# NCS_Wireless_Control_Card_MCU.net
KiCad netlist of a schematic drawn in Altium Designer
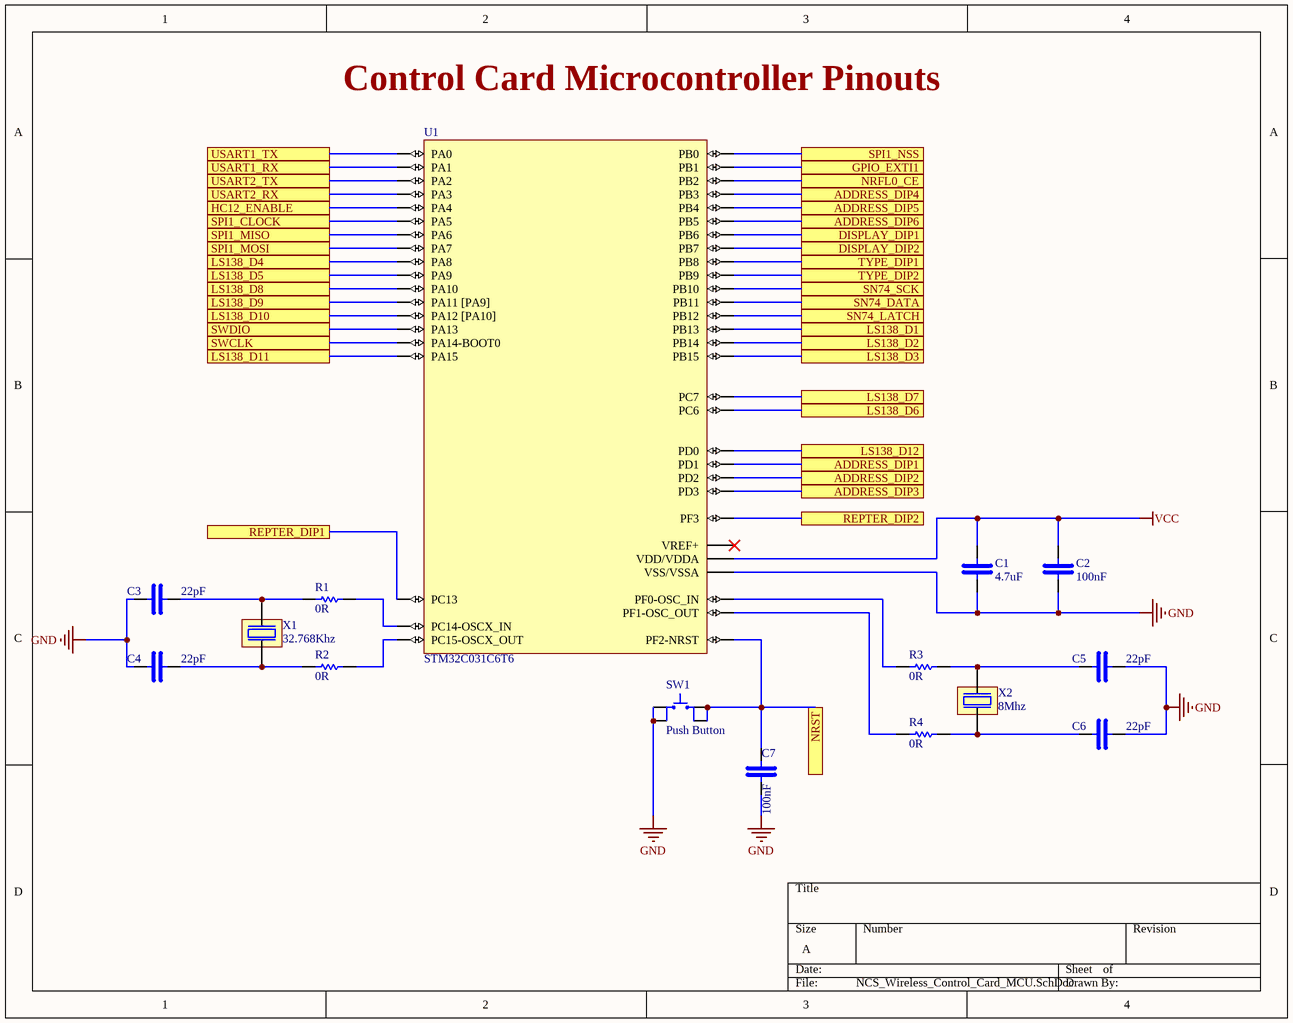
[diagram p0: NCS_Wireless_Control_Card_MCU.SchDoc]

(export (version "E")
  (design (tool "Eeschema 10.0.6"))
  (components
    (comp (ref "C1")
      (value "4.7uF")
      (footprint "C0805C209D3HACTU_2pF")
      (description "Multilayer Ceramic Capacitor, 4.7 uF, 25 V, ï¿½ 10%, X5R, 0805 [2012 Metric]")
      (fields
        (field (name "MANUFACTURER") "KEMET")
        (field (name "MANUFACTURER PART NUMBER") "C0805C475K3PACTU")
      )
      (libsource (lib "schlib") (part "C0805C475K3PACTU"))
    )
    (comp (ref "C2")
      (value "100nF")
      (footprint "C0805C104K3RACTU_100nF")
      (description "Multilayer Ceramic Capacitor, 0.1 uF, 25 V, ï¿½ 10%, X7R, 0805 [2012 Metric]")
      (fields
        (field (name "MANUFACTURER") "KEMET")
        (field (name "MANUFACTURER PART NUMBER") "C0805C104K3RACTU")
      )
      (libsource (lib "schlib") (part "C0805C104K3RACTU"))
    )
    (comp (ref "C3")
      (value "22pF")
      (footprint "C0805C209D3HACTU_2pF")
      (description "C0805C209D3HACTU_2pF")
      (fields
        (field (name "MANUFACTURER") "KEMET")
        (field (name "MANUFACTURER PART NUMBER") "C0805C209D3HACTU")
      )
      (libsource (lib "schlib") (part "C0805C209D3HACTU"))
    )
    (comp (ref "C4")
      (value "22pF")
      (footprint "C0805C209D3HACTU_2pF")
      (description "C0805C209D3HACTU_2pF")
      (fields
        (field (name "MANUFACTURER") "KEMET")
        (field (name "MANUFACTURER PART NUMBER") "C0805C209D3HACTU")
      )
      (libsource (lib "schlib") (part "C0805C209D3HACTU"))
    )
    (comp (ref "C5")
      (value "22pF")
      (footprint "C0805C209D3HACTU_2pF")
      (description "C0805C209D3HACTU_2pF")
      (fields
        (field (name "MANUFACTURER") "KEMET")
        (field (name "MANUFACTURER PART NUMBER") "C0805C209D3HACTU")
      )
      (libsource (lib "schlib") (part "C0805C209D3HACTU"))
    )
    (comp (ref "C6")
      (value "22pF")
      (footprint "C0805C209D3HACTU_2pF")
      (description "C0805C209D3HACTU_2pF")
      (fields
        (field (name "MANUFACTURER") "KEMET")
        (field (name "MANUFACTURER PART NUMBER") "C0805C209D3HACTU")
      )
      (libsource (lib "schlib") (part "C0805C209D3HACTU"))
    )
    (comp (ref "C7")
      (value "100nF")
      (footprint "C0805C104K3RACTU_100nF")
      (description "Multilayer Ceramic Capacitor, 0.1 uF, 25 V, ï¿½ 10%, X7R, 0805 [2012 Metric]")
      (fields
        (field (name "MANUFACTURER") "KEMET")
        (field (name "MANUFACTURER PART NUMBER") "C0805C104K3RACTU")
      )
      (libsource (lib "schlib") (part "C0805C104K3RACTU"))
    )
    (comp (ref "R1")
      (value "0R")
      (footprint "RC0805FR-7W330RL")
      (description "Res Thick Film 0805 330 Ohm 1% 0.25W(1/4W) ±200ppm/C Pad SMD T/R")
      (fields
        (field (name "MANUFACTURER") "Yageo")
        (field (name "MANUFACTURER PART NUMBER") "RC0805FR-7W330RL")
      )
      (libsource (lib "schlib") (part "RC0805FR-7W330RL"))
    )
    (comp (ref "R2")
      (value "0R")
      (footprint "RC0805FR-7W330RL")
      (description "Res Thick Film 0805 330 Ohm 1% 0.25W(1/4W) ±200ppm/C Pad SMD T/R")
      (fields
        (field (name "MANUFACTURER") "Yageo")
        (field (name "MANUFACTURER PART NUMBER") "RC0805FR-7W330RL")
      )
      (libsource (lib "schlib") (part "RC0805FR-7W330RL"))
    )
    (comp (ref "R3")
      (value "0R")
      (footprint "RC0805FR-7W330RL")
      (description "Res Thick Film 0805 330 Ohm 1% 0.25W(1/4W) ±200ppm/C Pad SMD T/R")
      (fields
        (field (name "MANUFACTURER") "Yageo")
        (field (name "MANUFACTURER PART NUMBER") "RC0805FR-7W330RL")
      )
      (libsource (lib "schlib") (part "RC0805FR-7W330RL"))
    )
    (comp (ref "R4")
      (value "0R")
      (footprint "RC0805FR-7W330RL")
      (description "Res Thick Film 0805 330 Ohm 1% 0.25W(1/4W) ±200ppm/C Pad SMD T/R")
      (fields
        (field (name "MANUFACTURER") "Yageo")
        (field (name "MANUFACTURER PART NUMBER") "RC0805FR-7W330RL")
      )
      (libsource (lib "schlib") (part "RC0805FR-7W330RL"))
    )
    (comp (ref "SW1")
      (value "Push Button")
      (footprint "PUSH BUTTON SMD")
      (libsource (lib "NCS_Wireless_Bed_Unit") (part "Tactile Switch SMD 4P 5.2x5.2x1.5mm - EVELTA"))
    )
    (comp (ref "U1")
      (value "STM32C031C6T6")
      (footprint "STM32C031C6T6-48N")
      (description "RISC Microcontroller, 32-Bit, FLASH, CORTEX-M4F CPU, 180MHz, CMOS, PBGA216")
      (fields (field (name "MANUFACTURER") "STMicroelectronics"))
      (libsource (lib "NCS_Wireless_Bed_Unit") (part "STM32C031C6T6"))
    )
    (comp (ref "X1")
      (value "32.768Khz")
      (footprint "32.768KHz")
      (libsource (lib "NCS_Wireless_Bed_Unit") (part "32.768 Khz RTC Crystal T38-SUNROM"))
    )
    (comp (ref "X2")
      (value "8Mhz")
      (footprint "8Mhz Crystal")
      (libsource (lib "NCS_Wireless_Bed_Unit") (part "8 Mhz Crystal HC-49US-SUNROM"))
    )
  )
  (nets
    (net (code "1") (name "/ADDRESS_DIP1") (class "Default")
      (node (ref "U1") (pin "39") (pinfunction "PD1_39") (pintype "bidirectional"))
    )
    (net (code "2") (name "/ADDRESS_DIP2") (class "Default")
      (node (ref "U1") (pin "40") (pinfunction "PD2_40") (pintype "bidirectional"))
    )
    (net (code "3") (name "/ADDRESS_DIP3") (class "Default")
      (node (ref "U1") (pin "41") (pinfunction "PD3_41") (pintype "bidirectional"))
    )
    (net (code "4") (name "/ADDRESS_DIP4") (class "Default")
      (node (ref "U1") (pin "42") (pinfunction "PB3_42") (pintype "bidirectional"))
    )
    (net (code "5") (name "/ADDRESS_DIP5") (class "Default")
      (node (ref "U1") (pin "43") (pinfunction "PB4_43") (pintype "bidirectional"))
    )
    (net (code "6") (name "/ADDRESS_DIP6") (class "Default")
      (node (ref "U1") (pin "44") (pinfunction "PB5_44") (pintype "bidirectional"))
    )
    (net (code "7") (name "/DISPLAY_DIP1") (class "Default")
      (node (ref "U1") (pin "45") (pinfunction "PB6_45") (pintype "bidirectional"))
    )
    (net (code "8") (name "/DISPLAY_DIP2") (class "Default")
      (node (ref "U1") (pin "46") (pinfunction "PB7_46") (pintype "bidirectional"))
    )
    (net (code "9") (name "/GPIO_EXTI1") (class "Default")
      (node (ref "U1") (pin "20") (pinfunction "PB1_20") (pintype "bidirectional"))
    )
    (net (code "10") (name "/HC12_ENABLE") (class "Default")
      (node (ref "U1") (pin "15") (pinfunction "PA4_15") (pintype "bidirectional"))
    )
    (net (code "11") (name "/LS138_D1") (class "Default")
      (node (ref "U1") (pin "25") (pinfunction "PB13_25") (pintype "bidirectional"))
    )
    (net (code "12") (name "/LS138_D2") (class "Default")
      (node (ref "U1") (pin "26") (pinfunction "PB14_26") (pintype "bidirectional"))
    )
    (net (code "13") (name "/LS138_D3") (class "Default")
      (node (ref "U1") (pin "27") (pinfunction "PB15_27") (pintype "bidirectional"))
    )
    (net (code "14") (name "/LS138_D4") (class "Default")
      (node (ref "U1") (pin "28") (pinfunction "PA8_28") (pintype "bidirectional"))
    )
    (net (code "15") (name "/LS138_D5") (class "Default")
      (node (ref "U1") (pin "29") (pinfunction "PA9_29") (pintype "bidirectional"))
    )
    (net (code "16") (name "/LS138_D6") (class "Default")
      (node (ref "U1") (pin "30") (pinfunction "PC6_30") (pintype "bidirectional"))
    )
    (net (code "17") (name "/LS138_D7") (class "Default")
      (node (ref "U1") (pin "31") (pinfunction "PC7_31") (pintype "bidirectional"))
    )
    (net (code "18") (name "/LS138_D8") (class "Default")
      (node (ref "U1") (pin "32") (pinfunction "PA10_32") (pintype "bidirectional"))
    )
    (net (code "19") (name "/LS138_D9") (class "Default")
      (node (ref "U1") (pin "33") (pinfunction "PA11_[PA9]_33") (pintype "bidirectional"))
    )
    (net (code "20") (name "/LS138_D10") (class "Default")
      (node (ref "U1") (pin "34") (pinfunction "PA12_[PA10]_34") (pintype "bidirectional"))
    )
    (net (code "21") (name "/LS138_D11") (class "Default")
      (node (ref "U1") (pin "37") (pinfunction "PA15_37") (pintype "bidirectional"))
    )
    (net (code "22") (name "/LS138_D12") (class "Default")
      (node (ref "U1") (pin "38") (pinfunction "PD0_38") (pintype "bidirectional"))
    )
    (net (code "23") (name "/NRFL0_CE") (class "Default")
      (node (ref "U1") (pin "21") (pinfunction "PB2_21") (pintype "bidirectional"))
    )
    (net (code "24") (name "/NRST") (class "Default")
      (node (ref "C7") (pin "2") (pinfunction "2_2") (pintype "passive"))
      (node (ref "SW1") (pin "3") (pinfunction "3_3") (pintype "passive"))
      (node (ref "SW1") (pin "4") (pinfunction "4_4") (pintype "passive"))
      (node (ref "U1") (pin "10") (pinfunction "PF2-NRST_10") (pintype "bidirectional"))
    )
    (net (code "25") (name "/REPTER_DIP1") (class "Default")
      (node (ref "U1") (pin "1") (pinfunction "PC13_1") (pintype "bidirectional"))
    )
    (net (code "26") (name "/REPTER_DIP2") (class "Default")
      (node (ref "U1") (pin "4") (pinfunction "PF3_4") (pintype "bidirectional"))
    )
    (net (code "27") (name "/SN74_DATA") (class "Default")
      (node (ref "U1") (pin "23") (pinfunction "PB11_23") (pintype "bidirectional"))
    )
    (net (code "28") (name "/SN74_LATCH") (class "Default")
      (node (ref "U1") (pin "24") (pinfunction "PB12_24") (pintype "bidirectional"))
    )
    (net (code "29") (name "/SN74_SCK") (class "Default")
      (node (ref "U1") (pin "22") (pinfunction "PB10_22") (pintype "bidirectional"))
    )
    (net (code "30") (name "/SPI1_CLOCK") (class "Default")
      (node (ref "U1") (pin "16") (pinfunction "PA5_16") (pintype "bidirectional"))
    )
    (net (code "31") (name "/SPI1_MISO") (class "Default")
      (node (ref "U1") (pin "17") (pinfunction "PA6_17") (pintype "bidirectional"))
    )
    (net (code "32") (name "/SPI1_MOSI") (class "Default")
      (node (ref "U1") (pin "18") (pinfunction "PA7_18") (pintype "bidirectional"))
    )
    (net (code "33") (name "/SPI1_NSS") (class "Default")
      (node (ref "U1") (pin "19") (pinfunction "PB0_19") (pintype "bidirectional"))
    )
    (net (code "34") (name "/SWCLK") (class "Default")
      (node (ref "U1") (pin "36") (pinfunction "PA14-BOOT0_36") (pintype "bidirectional"))
    )
    (net (code "35") (name "/SWDIO") (class "Default")
      (node (ref "U1") (pin "35") (pinfunction "PA13_35") (pintype "bidirectional"))
    )
    (net (code "36") (name "/TYPE_DIP1") (class "Default")
      (node (ref "U1") (pin "47") (pinfunction "PB8_47") (pintype "bidirectional"))
    )
    (net (code "37") (name "/TYPE_DIP2") (class "Default")
      (node (ref "U1") (pin "48") (pinfunction "PB9_48") (pintype "bidirectional"))
    )
    (net (code "38") (name "/USART1_RX") (class "Default")
      (node (ref "U1") (pin "12") (pinfunction "PA1_12") (pintype "bidirectional"))
    )
    (net (code "39") (name "/USART1_TX") (class "Default")
      (node (ref "U1") (pin "11") (pinfunction "PA0_11") (pintype "bidirectional"))
    )
    (net (code "40") (name "/USART2_RX") (class "Default")
      (node (ref "U1") (pin "14") (pinfunction "PA3_14") (pintype "bidirectional"))
    )
    (net (code "41") (name "/USART2_TX") (class "Default")
      (node (ref "U1") (pin "13") (pinfunction "PA2_13") (pintype "bidirectional"))
    )
    (net (code "42") (name "GND") (class "Default")
      (node (ref "C1") (pin "1") (pinfunction "1_1") (pintype "passive"))
      (node (ref "C2") (pin "1") (pinfunction "1_1") (pintype "passive"))
      (node (ref "C3") (pin "2") (pinfunction "2_2") (pintype "passive"))
      (node (ref "C4") (pin "2") (pinfunction "2_2") (pintype "passive"))
      (node (ref "C5") (pin "1") (pinfunction "1_1") (pintype "passive"))
      (node (ref "C6") (pin "1") (pinfunction "1_1") (pintype "passive"))
      (node (ref "C7") (pin "1") (pinfunction "1_1") (pintype "passive"))
      (node (ref "SW1") (pin "1") (pinfunction "1_1") (pintype "passive"))
      (node (ref "SW1") (pin "2") (pinfunction "2_2") (pintype "passive"))
      (node (ref "U1") (pin "7") (pinfunction "VSS/VSSA_7") (pintype "power_in"))
    )
    (net (code "43") (name "Net-(C3-Pad1)") (class "Default")
      (node (ref "C3") (pin "1") (pinfunction "1_1") (pintype "passive"))
      (node (ref "R1") (pin "1") (pinfunction "1_1") (pintype "passive"))
      (node (ref "X1") (pin "2") (pinfunction "2_2") (pintype "passive"))
    )
    (net (code "44") (name "Net-(C4-Pad1)") (class "Default")
      (node (ref "C4") (pin "1") (pinfunction "1_1") (pintype "passive"))
      (node (ref "R2") (pin "1") (pinfunction "1_1") (pintype "passive"))
      (node (ref "X1") (pin "1") (pinfunction "1_1") (pintype "passive"))
    )
    (net (code "45") (name "Net-(C5-Pad2)") (class "Default")
      (node (ref "C5") (pin "2") (pinfunction "2_2") (pintype "passive"))
      (node (ref "R3") (pin "2") (pinfunction "2_2") (pintype "passive"))
      (node (ref "X2") (pin "2") (pinfunction "2_2") (pintype "passive"))
    )
    (net (code "46") (name "Net-(C6-Pad2)") (class "Default")
      (node (ref "C6") (pin "2") (pinfunction "2_2") (pintype "passive"))
      (node (ref "R4") (pin "2") (pinfunction "2_2") (pintype "passive"))
      (node (ref "X2") (pin "1") (pinfunction "1_1") (pintype "passive"))
    )
    (net (code "47") (name "Net-(U1-PC14-OSCX_IN)") (class "Default")
      (node (ref "R1") (pin "2") (pinfunction "2_2") (pintype "passive"))
      (node (ref "U1") (pin "2") (pinfunction "PC14-OSCX_IN_2") (pintype "bidirectional"))
    )
    (net (code "48") (name "Net-(U1-PC15-OSCX_OUT)") (class "Default")
      (node (ref "R2") (pin "2") (pinfunction "2_2") (pintype "passive"))
      (node (ref "U1") (pin "3") (pinfunction "PC15-OSCX_OUT_3") (pintype "bidirectional"))
    )
    (net (code "49") (name "Net-(U1-PF0-OSC_IN)") (class "Default")
      (node (ref "R3") (pin "1") (pinfunction "1_1") (pintype "passive"))
      (node (ref "U1") (pin "8") (pinfunction "PF0-OSC_IN_8") (pintype "bidirectional"))
    )
    (net (code "50") (name "Net-(U1-PF1-OSC_OUT)") (class "Default")
      (node (ref "R4") (pin "1") (pinfunction "1_1") (pintype "passive"))
      (node (ref "U1") (pin "9") (pinfunction "PF1-OSC_OUT_9") (pintype "bidirectional"))
    )
    (net (code "51") (name "VCC") (class "Default")
      (node (ref "C1") (pin "2") (pinfunction "2_2") (pintype "passive"))
      (node (ref "C2") (pin "2") (pinfunction "2_2") (pintype "passive"))
      (node (ref "U1") (pin "6") (pinfunction "VDD/VDDA_6") (pintype "power_in"))
    )
    (net (code "52") (name "unconnected-(U1-VREF+-Pad5)") (class "Default")
      (node (ref "U1") (pin "5") (pinfunction "VREF+_5") (pintype "power_in+no_connect"))
    )
  )
)
